# SNES_DRONE_LEVEL_SHIFTER_2.net
KiCad netlist of a schematic drawn in Altium Designer
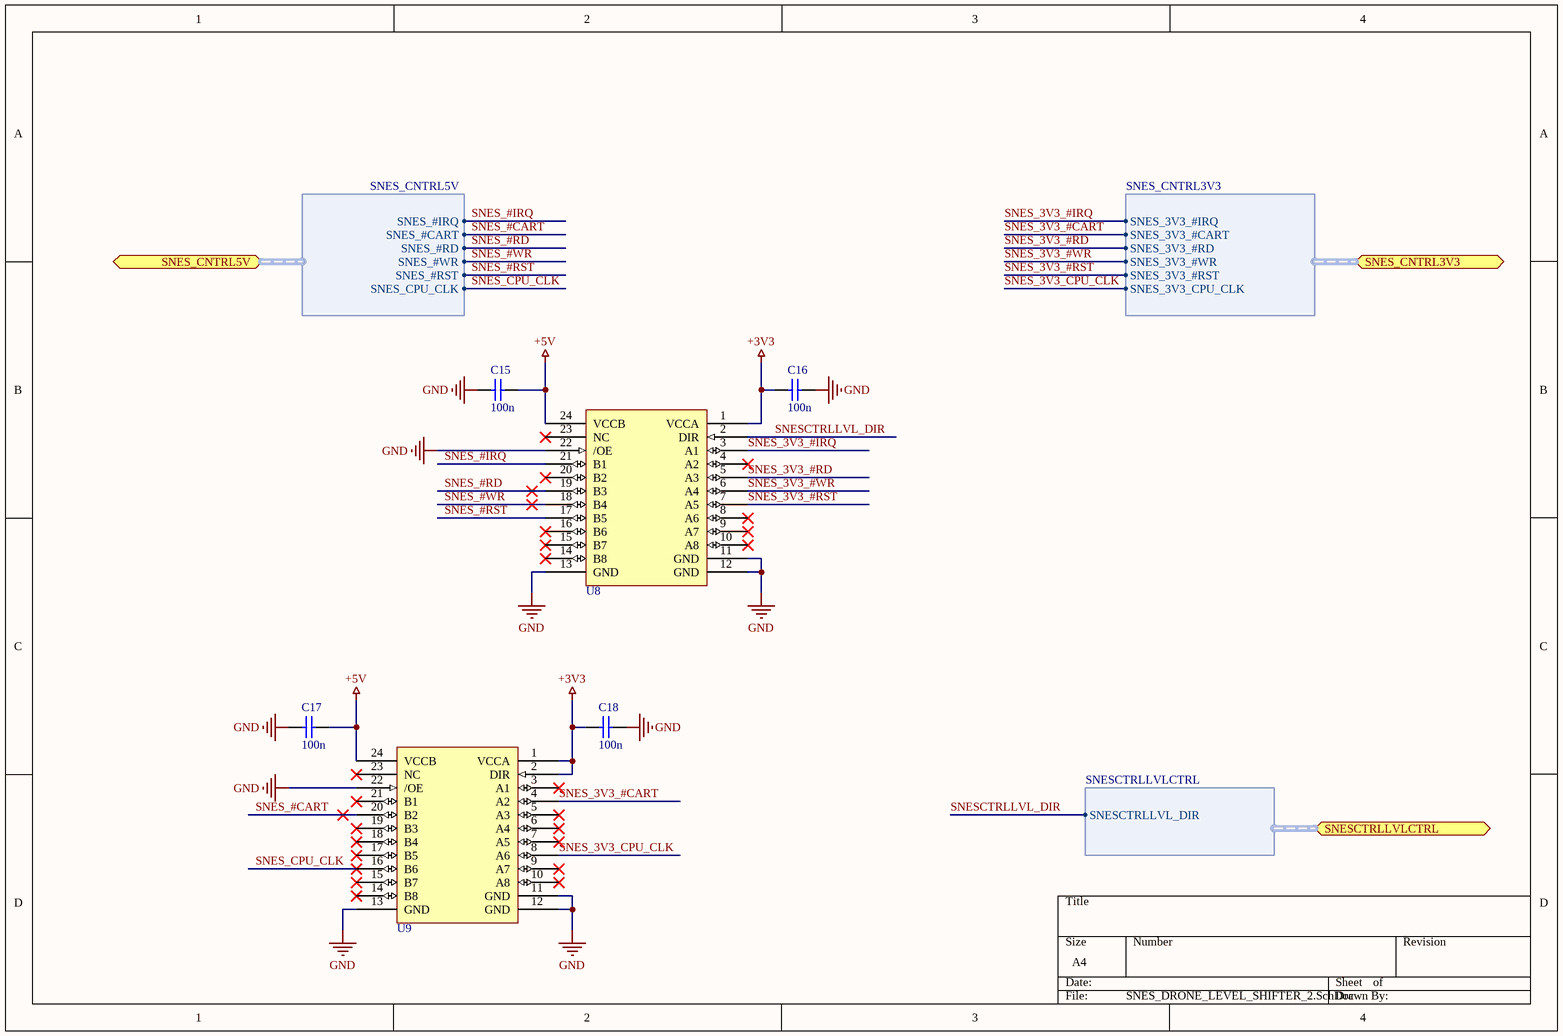
[diagram p0: SNES_DRONE_LEVEL_SHIFTER_2.SchDoc]

(export (version "E")
  (design (tool "Eeschema 10.0.6"))
  (components
    (comp (ref "C15")
      (value "100n")
      (footprint "cap_0603")
      (description "Capacitor")
      (fields (field (name "Comment") "cap_0603"))
      (libsource (lib "mycomponents") (part "cap_0603"))
    )
    (comp (ref "C16")
      (value "100n")
      (footprint "cap_0603")
      (description "Capacitor")
      (fields (field (name "Comment") "cap_0603"))
      (libsource (lib "mycomponents") (part "cap_0603"))
    )
    (comp (ref "C17")
      (value "100n")
      (footprint "cap_0603")
      (description "Capacitor")
      (fields (field (name "Comment") "cap_0603"))
      (libsource (lib "mycomponents") (part "cap_0603"))
    )
    (comp (ref "C18")
      (value "100n")
      (footprint "cap_0603")
      (description "Capacitor")
      (fields (field (name "Comment") "cap_0603"))
      (libsource (lib "mycomponents") (part "cap_0603"))
    )
    (comp (ref "U8")
      (value "IC_SN74LVCC3245APWR")
      (footprint "TSSOP24")
      (description "Bus-Transceiver, Produktreihe LVC, 8 Eingänge, 50mA, 7ns, 2.3V bis 5.5V, TSSOP 24")
      (libsource (lib "mycomponents") (part "IC_SN74LVCC3245APWR"))
    )
    (comp (ref "U9")
      (value "IC_SN74LVCC3245APWR")
      (footprint "TSSOP24")
      (description "Bus-Transceiver, Produktreihe LVC, 8 Eingänge, 50mA, 7ns, 2.3V bis 5.5V, TSSOP 24")
      (libsource (lib "mycomponents") (part "IC_SN74LVCC3245APWR"))
    )
  )
  (nets
    (net (code "4") (name "+3V3") (class "Default")
      (node (ref "C16") (pin "2") (pinfunction "2_2") (pintype "passive"))
      (node (ref "C18") (pin "2") (pinfunction "2_2") (pintype "passive"))
      (node (ref "U8") (pin "1") (pinfunction "VCCA_1") (pintype "power_in"))
      (node (ref "U9") (pin "1") (pinfunction "VCCA_1") (pintype "power_in"))
      (node (ref "U9") (pin "2") (pinfunction "DIR_2") (pintype "input"))
    )
    (net (code "5") (name "+5V") (class "Default")
      (node (ref "C15") (pin "1") (pinfunction "1_1") (pintype "passive"))
      (node (ref "C17") (pin "1") (pinfunction "1_1") (pintype "passive"))
      (node (ref "U8") (pin "24") (pinfunction "VCCB_24") (pintype "power_in"))
      (node (ref "U9") (pin "24") (pinfunction "VCCB_24") (pintype "power_in"))
    )
    (net (code "6") (name "/SNESCTRLLVL_DIR") (class "Default")
      (node (ref "U8") (pin "2") (pinfunction "DIR_2") (pintype "input"))
    )
    (net (code "7") (name "/SNES_#CART") (class "Default")
      (node (ref "U9") (pin "20") (pinfunction "B2_20") (pintype "bidirectional"))
    )
    (net (code "8") (name "/SNES_#IRQ") (class "Default")
      (node (ref "U8") (pin "21") (pinfunction "B1_21") (pintype "bidirectional"))
    )
    (net (code "9") (name "/SNES_#RD") (class "Default")
      (node (ref "U8") (pin "19") (pinfunction "B3_19") (pintype "bidirectional"))
    )
    (net (code "10") (name "/SNES_#RST") (class "Default")
      (node (ref "U8") (pin "17") (pinfunction "B5_17") (pintype "bidirectional"))
    )
    (net (code "11") (name "/SNES_#WR") (class "Default")
      (node (ref "U8") (pin "18") (pinfunction "B4_18") (pintype "bidirectional"))
    )
    (net (code "12") (name "/SNES_3V3_#CART") (class "Default")
      (node (ref "U9") (pin "4") (pinfunction "A2_4") (pintype "bidirectional"))
    )
    (net (code "13") (name "/SNES_3V3_#IRQ") (class "Default")
      (node (ref "U8") (pin "3") (pinfunction "A1_3") (pintype "bidirectional"))
    )
    (net (code "14") (name "/SNES_3V3_#RD") (class "Default")
      (node (ref "U8") (pin "5") (pinfunction "A3_5") (pintype "bidirectional"))
    )
    (net (code "15") (name "/SNES_3V3_#RST") (class "Default")
      (node (ref "U8") (pin "7") (pinfunction "A5_7") (pintype "bidirectional"))
    )
    (net (code "16") (name "/SNES_3V3_#WR") (class "Default")
      (node (ref "U8") (pin "6") (pinfunction "A4_6") (pintype "bidirectional"))
    )
    (net (code "17") (name "/SNES_3V3_CPU_CLK") (class "Default")
      (node (ref "U9") (pin "8") (pinfunction "A6_8") (pintype "bidirectional"))
    )
    (net (code "18") (name "/SNES_CPU_CLK") (class "Default")
      (node (ref "U9") (pin "16") (pinfunction "B6_16") (pintype "bidirectional"))
    )
    (net (code "22") (name "GND") (class "Default")
      (node (ref "C15") (pin "2") (pinfunction "2_2") (pintype "passive"))
      (node (ref "C16") (pin "1") (pinfunction "1_1") (pintype "passive"))
      (node (ref "C17") (pin "2") (pinfunction "2_2") (pintype "passive"))
      (node (ref "C18") (pin "1") (pinfunction "1_1") (pintype "passive"))
      (node (ref "U8") (pin "11") (pinfunction "GND_11") (pintype "power_in"))
      (node (ref "U8") (pin "12") (pinfunction "GND_12") (pintype "power_in"))
      (node (ref "U8") (pin "13") (pinfunction "GND_13") (pintype "power_in"))
      (node (ref "U8") (pin "22") (pinfunction "/OE_22") (pintype "input"))
      (node (ref "U9") (pin "11") (pinfunction "GND_11") (pintype "power_in"))
      (node (ref "U9") (pin "12") (pinfunction "GND_12") (pintype "power_in"))
      (node (ref "U9") (pin "13") (pinfunction "GND_13") (pintype "power_in"))
      (node (ref "U9") (pin "22") (pinfunction "/OE_22") (pintype "input"))
    )
    (net (code "23") (name "unconnected-(U8-A2-Pad4)") (class "Default")
      (node (ref "U8") (pin "4") (pinfunction "A2_4") (pintype "bidirectional+no_connect"))
    )
    (net (code "24") (name "unconnected-(U8-A6-Pad8)") (class "Default")
      (node (ref "U8") (pin "8") (pinfunction "A6_8") (pintype "bidirectional+no_connect"))
    )
    (net (code "25") (name "unconnected-(U8-A7-Pad9)") (class "Default")
      (node (ref "U8") (pin "9") (pinfunction "A7_9") (pintype "bidirectional+no_connect"))
    )
    (net (code "26") (name "unconnected-(U8-A8-Pad10)") (class "Default")
      (node (ref "U8") (pin "10") (pinfunction "A8_10") (pintype "bidirectional+no_connect"))
    )
    (net (code "27") (name "unconnected-(U8-B2-Pad20)") (class "Default")
      (node (ref "U8") (pin "20") (pinfunction "B2_20") (pintype "bidirectional+no_connect"))
    )
    (net (code "28") (name "unconnected-(U8-B6-Pad16)") (class "Default")
      (node (ref "U8") (pin "16") (pinfunction "B6_16") (pintype "bidirectional+no_connect"))
    )
    (net (code "29") (name "unconnected-(U8-B7-Pad15)") (class "Default")
      (node (ref "U8") (pin "15") (pinfunction "B7_15") (pintype "bidirectional+no_connect"))
    )
    (net (code "30") (name "unconnected-(U8-B8-Pad14)") (class "Default")
      (node (ref "U8") (pin "14") (pinfunction "B8_14") (pintype "bidirectional+no_connect"))
    )
    (net (code "31") (name "unconnected-(U8-NC-Pad23)") (class "Default")
      (node (ref "U8") (pin "23") (pinfunction "NC_23") (pintype "passive+no_connect"))
    )
    (net (code "32") (name "unconnected-(U9-A1-Pad3)") (class "Default")
      (node (ref "U9") (pin "3") (pinfunction "A1_3") (pintype "bidirectional+no_connect"))
    )
    (net (code "33") (name "unconnected-(U9-A3-Pad5)") (class "Default")
      (node (ref "U9") (pin "5") (pinfunction "A3_5") (pintype "bidirectional+no_connect"))
    )
    (net (code "34") (name "unconnected-(U9-A4-Pad6)") (class "Default")
      (node (ref "U9") (pin "6") (pinfunction "A4_6") (pintype "bidirectional+no_connect"))
    )
    (net (code "35") (name "unconnected-(U9-A5-Pad7)") (class "Default")
      (node (ref "U9") (pin "7") (pinfunction "A5_7") (pintype "bidirectional+no_connect"))
    )
    (net (code "36") (name "unconnected-(U9-A7-Pad9)") (class "Default")
      (node (ref "U9") (pin "9") (pinfunction "A7_9") (pintype "bidirectional+no_connect"))
    )
    (net (code "37") (name "unconnected-(U9-A8-Pad10)") (class "Default")
      (node (ref "U9") (pin "10") (pinfunction "A8_10") (pintype "bidirectional+no_connect"))
    )
    (net (code "38") (name "unconnected-(U9-B1-Pad21)") (class "Default")
      (node (ref "U9") (pin "21") (pinfunction "B1_21") (pintype "bidirectional+no_connect"))
    )
    (net (code "39") (name "unconnected-(U9-B3-Pad19)") (class "Default")
      (node (ref "U9") (pin "19") (pinfunction "B3_19") (pintype "bidirectional+no_connect"))
    )
    (net (code "40") (name "unconnected-(U9-B4-Pad18)") (class "Default")
      (node (ref "U9") (pin "18") (pinfunction "B4_18") (pintype "bidirectional+no_connect"))
    )
    (net (code "41") (name "unconnected-(U9-B5-Pad17)") (class "Default")
      (node (ref "U9") (pin "17") (pinfunction "B5_17") (pintype "bidirectional+no_connect"))
    )
    (net (code "42") (name "unconnected-(U9-B7-Pad15)") (class "Default")
      (node (ref "U9") (pin "15") (pinfunction "B7_15") (pintype "bidirectional+no_connect"))
    )
    (net (code "43") (name "unconnected-(U9-B8-Pad14)") (class "Default")
      (node (ref "U9") (pin "14") (pinfunction "B8_14") (pintype "bidirectional+no_connect"))
    )
    (net (code "44") (name "unconnected-(U9-NC-Pad23)") (class "Default")
      (node (ref "U9") (pin "23") (pinfunction "NC_23") (pintype "passive+no_connect"))
    )
  )
)
